# Sheet1.net
KiCad netlist of a schematic drawn in Altium Designer
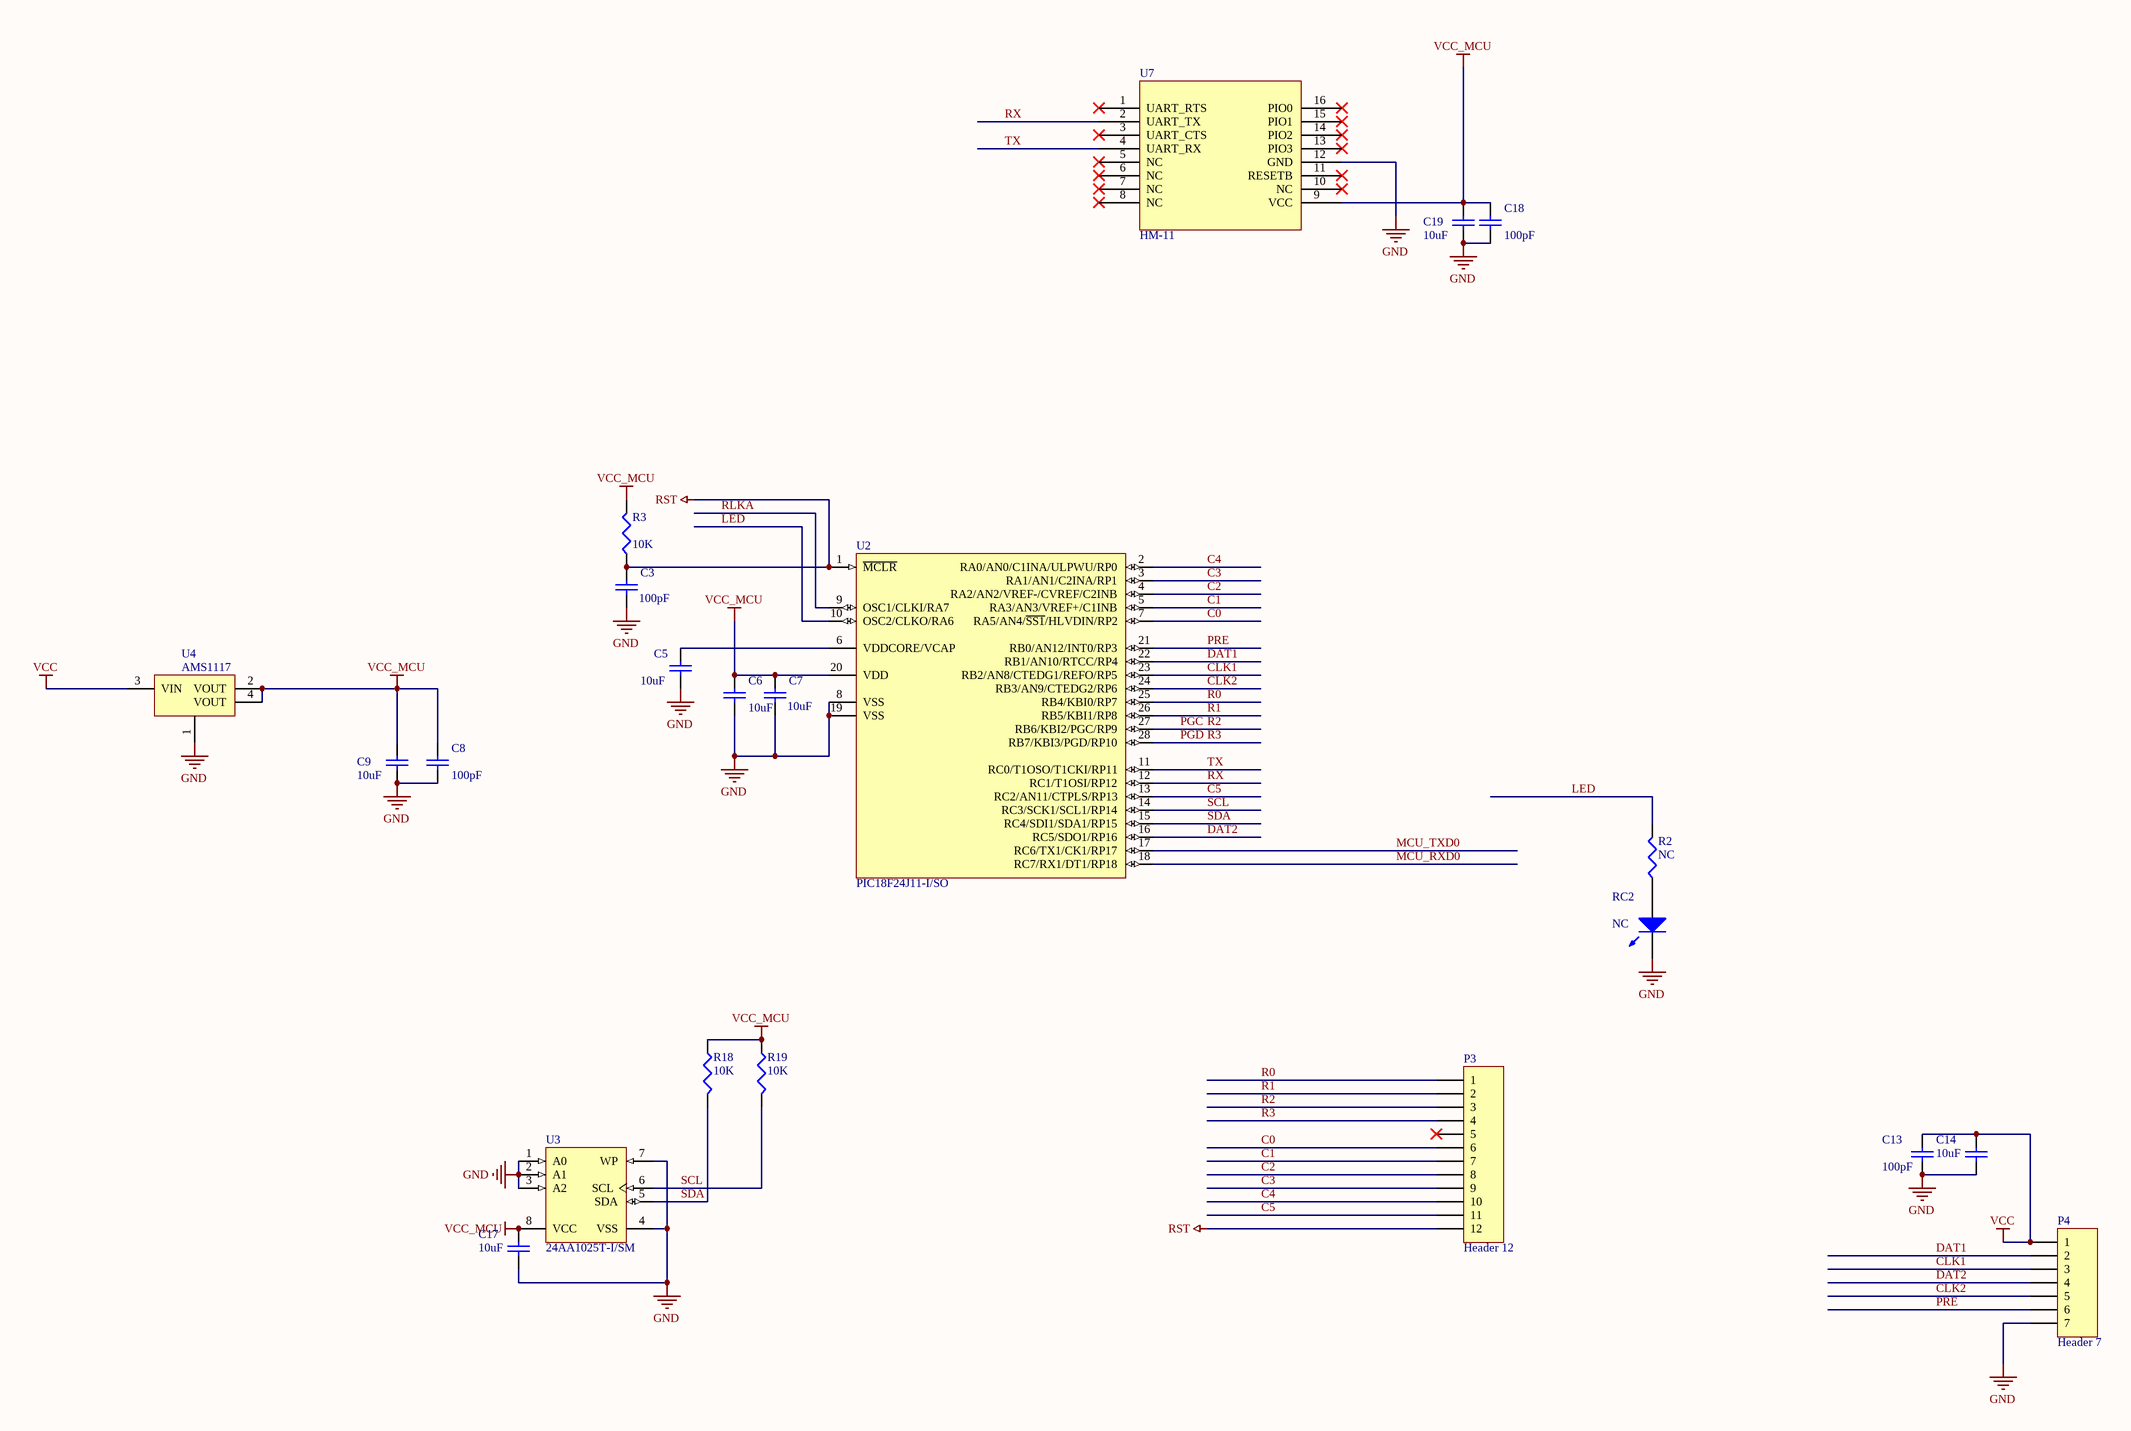
[diagram p0: Sheet1.SchDoc]

(export (version "E")
  (design (tool "Eeschema 10.0.6"))
  (components
    (comp (ref "C3")
      (value "100pF")
      (footprint "CAPC2013X05N")
      (description "0.10µF 50V Ceramic Capacitor Y5V (F) 0805 (2012 Metric) 0.079\" L x 0.049\" W (2.00mm x 1.25mm)")
      (fields (field (name "Comment") "CL21F104ZBCNNNC"))
      (libsource (lib "Miscellaneous Devices") (part "Cap Semi"))
    )
    (comp (ref "C5")
      (value "10uF")
      (footprint "CAPC2013X05N")
      (description "10µF 6.3V Ceramic Capacitor X5R 0805 (2012 Metric) 0.079\" L x 0.049\" W (2.00mm x 1.25mm)")
      (fields (field (name "Comment") "GRM219R60J106KE19D"))
      (libsource (lib "Miscellaneous Devices") (part "Cap Semi"))
    )
    (comp (ref "C6")
      (value "10uF")
      (footprint "CAPC2013X05N")
      (description "10µF 6.3V Ceramic Capacitor X5R 0805 (2012 Metric) 0.079\" L x 0.049\" W (2.00mm x 1.25mm)")
      (fields (field (name "Comment") "GRM219R60J106KE19D"))
      (libsource (lib "Miscellaneous Devices") (part "Cap Semi"))
    )
    (comp (ref "C7")
      (value "10uF")
      (footprint "CAPC2013X05N")
      (description "0.10µF 50V Cera2012 Metric) 0.079\" L x 0.049\" W (2.00mm x 1.25mm)")
      (fields (field (name "Comment") "GRM219R60J106KE19D"))
      (libsource (lib "Miscellaneous Devices") (part "Cap Semi"))
    )
    (comp (ref "C8")
      (value "100pF")
      (footprint "RESC2012L")
      (description "0.10µF 50V Ceramic Capacitor Y5V (F) 0805 (2012 Metric) 0.079\" L x 0.049\" W (2.00mm x 1.25mm)")
      (fields (field (name "Comment") "CL21F104ZBCNNNC"))
      (libsource (lib "Miscellaneous Devices") (part "Cap"))
    )
    (comp (ref "C9")
      (value "10uF")
      (footprint "RESC2012L")
      (description "10µF 6.3V Ceramic Capacitor X5R 0805 (2012 Metric) 0.079\" L x 0.049\" W (2.00mm x 1.25mm)")
      (fields (field (name "Comment") "GRM219R60J106KE19D"))
      (libsource (lib "Miscellaneous Devices") (part "Cap"))
    )
    (comp (ref "C13")
      (value "100pF")
      (footprint "RESC2012L")
      (description "0.10µF 50V Ceramic Capacitor Y5V (F) 0805 (2012 Metric) 0.079\" L x 0.049\" W (2.00mm x 1.25mm)")
      (fields (field (name "Comment") "CL21F104ZBCNNNC"))
      (libsource (lib "Miscellaneous Devices") (part "Cap"))
    )
    (comp (ref "C14")
      (value "10uF")
      (footprint "RESC2012L")
      (description "10µF 6.3V Ceramic Capacitor X5R 0805 (2012 Metric) 0.079\" L x 0.049\" W (2.00mm x 1.25mm)")
      (fields (field (name "Comment") "GRM219R60J106KE19D"))
      (libsource (lib "Miscellaneous Devices") (part "Cap"))
    )
    (comp (ref "C17")
      (value "10uF")
      (footprint "RESC2012L")
      (description "10µF 6.3V Ceramic Capacitor X5R 0805 (2012 Metric) 0.079\" L x 0.049\" W (2.00mm x 1.25mm)")
      (fields (field (name "Comment") "GRM219R60J106KE19D"))
      (libsource (lib "Miscellaneous Devices") (part "Cap"))
    )
    (comp (ref "C18")
      (value "100pF")
      (footprint "CAPC2013X05N")
      (description "0.10µF 50V Ceramic Capacitor Y5V (F) 0805 (2012 Metric) 0.079\" L x 0.049\" W (2.00mm x 1.25mm)")
      (fields (field (name "Comment") "CL21F104ZBCNNNC"))
      (libsource (lib "Miscellaneous Devices") (part "Cap"))
    )
    (comp (ref "C19")
      (value "10uF")
      (footprint "CAPC2013X05N")
      (description "10µF 6.3V Ceramic Capacitor X5R 0805 (2012 Metric) 0.079\" L x 0.049\" W (2.00mm x 1.25mm)")
      (fields (field (name "Comment") "GRM219R60J106KE19D"))
      (libsource (lib "Miscellaneous Devices") (part "Cap"))
    )
    (comp (ref "P3")
      (value "Header 12")
      (footprint "HDR1X12")
      (description "Header, 12-Pin")
      (fields (field (name "PUBLISHER") "Altium Limited"))
      (libsource (lib "Miscellaneous Connectors") (part "Header 12"))
    )
    (comp (ref "P4")
      (value "Header 7")
      (footprint "HDR1X7")
      (description "Header, 7-Pin")
      (fields (field (name "PUBLISHER") "Altium Limited"))
      (libsource (lib "Miscellaneous Connectors") (part "Header 7"))
    )
    (comp (ref "R2")
      (value "NC")
      (footprint "RESC2012L")
      (fields (field (name "PUBLISHER") "Altium Limited"))
      (libsource (lib "Miscellaneous Devices") (part "Res3"))
    )
    (comp (ref "R3")
      (value "10K")
      (footprint "RESC2013X05N")
      (description "RES SMD 10K OHM 5% 1/8W 0805")
      (fields (field (name "Comment") "ERJ-6GEYJ103V"))
      (libsource (lib "Miscellaneous Devices") (part "Res3"))
    )
    (comp (ref "R18")
      (value "10K")
      (footprint "RESC2012L")
      (description "RES SMD 10K OHM 5% 1/8W 0805")
      (fields (field (name "Comment") "ERJ-6GEYJ103V"))
      (libsource (lib "Miscellaneous Devices") (part "Res3"))
    )
    (comp (ref "R19")
      (value "10K")
      (footprint "RESC2012L")
      (description "RES SMD 10K OHM 5% 1/8W 0805")
      (fields (field (name "Comment") "ERJ-6GEYJ103V"))
      (libsource (lib "Miscellaneous Devices") (part "Res3"))
    )
    (comp (ref "RC2")
      (value "NC")
      (footprint "CD3216-1206")
      (description "LED BLUE THRU BOARD 1206")
      (libsource (lib "AM335X_ZCZ") (part "LEDRED1206"))
    )
    (comp (ref "U2")
      (value "PIC18F24J11-I/SO")
      (footprint "SOIC-SO28_N")
      (fields (field (name "PUBLISHER") "Altium Limited"))
      (libsource (lib "Microchip Microcontroller 8-Bit PIC18") (part "PIC18F24J11-I/SO"))
    )
    (comp (ref "U3")
      (value "24AA1025T-I/SM")
      (footprint "SOIJ-SM8_N")
      (description "1 Mbit, 400kHz, 1.7V, I2C Serial EEPROM, 8-Pin SOIC 208mil, Industrial Temperature, Tape and Reel")
      (fields (field (name "PUBLISHER") "Altium Limited"))
      (libsource (lib "Microchip Memory I2C Serial EEPROM") (part "24AA1025T-I/SM"))
    )
    (comp (ref "U4")
      (value "AMS1117")
      (footprint "SOT223-4M")
      (description "Adjustable Precision Shunt Regulator")
      (fields (field (name "PUBLISHER") "Altium Limited"))
      (libsource (lib "Schlib1") (part "AMS1117"))
    )
    (comp (ref "U7") (value "HM-11") (footprint "HM-11") (libsource (lib "Schlib1") (part "HM-11")))
  )
  (nets
    (net (code "1") (name "/C0") (class "Default")
      (node (ref "P3") (pin "6") (pinfunction "6_6") (pintype "passive"))
      (node (ref "U2") (pin "7") (pinfunction "RA5/AN4/~{SS1}/HLVDIN/RP2_7") (pintype "bidirectional"))
    )
    (net (code "2") (name "/C1") (class "Default")
      (node (ref "P3") (pin "7") (pinfunction "7_7") (pintype "passive"))
      (node (ref "U2") (pin "5") (pinfunction "RA3/AN3/VREF+/C1INB_5") (pintype "bidirectional"))
    )
    (net (code "3") (name "/C2") (class "Default")
      (node (ref "P3") (pin "8") (pinfunction "8_8") (pintype "passive"))
      (node (ref "U2") (pin "4") (pinfunction "RA2/AN2/VREF-/CVREF/C2INB_4") (pintype "bidirectional"))
    )
    (net (code "4") (name "/C3") (class "Default")
      (node (ref "P3") (pin "9") (pinfunction "9_9") (pintype "passive"))
      (node (ref "U2") (pin "3") (pinfunction "RA1/AN1/C2INA/RP1_3") (pintype "bidirectional"))
    )
    (net (code "5") (name "/C4") (class "Default")
      (node (ref "P3") (pin "10") (pinfunction "10_10") (pintype "passive"))
      (node (ref "U2") (pin "2") (pinfunction "RA0/AN0/C1INA/ULPWU/RP0_2") (pintype "bidirectional"))
    )
    (net (code "6") (name "/C5") (class "Default")
      (node (ref "P3") (pin "11") (pinfunction "11_11") (pintype "passive"))
      (node (ref "U2") (pin "13") (pinfunction "RC2/AN11/CTPLS/RP13_13") (pintype "bidirectional"))
    )
    (net (code "7") (name "/CLK1") (class "Default")
      (node (ref "P4") (pin "3") (pinfunction "3_3") (pintype "passive"))
      (node (ref "U2") (pin "23") (pinfunction "RB2/AN8/CTEDG1/REFO/RP5_23") (pintype "bidirectional"))
    )
    (net (code "8") (name "/CLK2") (class "Default")
      (node (ref "P4") (pin "5") (pinfunction "5_5") (pintype "passive"))
      (node (ref "U2") (pin "24") (pinfunction "RB3/AN9/CTEDG2/RP6_24") (pintype "bidirectional"))
    )
    (net (code "9") (name "/DAT1") (class "Default")
      (node (ref "P4") (pin "2") (pinfunction "2_2") (pintype "passive"))
      (node (ref "U2") (pin "22") (pinfunction "RB1/AN10/RTCC/RP4_22") (pintype "bidirectional"))
    )
    (net (code "10") (name "/DAT2") (class "Default")
      (node (ref "P4") (pin "4") (pinfunction "4_4") (pintype "passive"))
      (node (ref "U2") (pin "16") (pinfunction "RC5/SDO1/RP16_16") (pintype "bidirectional"))
    )
    (net (code "11") (name "/LED") (class "Default")
      (node (ref "R2") (pin "1") (pinfunction "1_1") (pintype "passive"))
      (node (ref "U2") (pin "10") (pinfunction "OSC2/CLKO/RA6_10") (pintype "bidirectional"))
    )
    (net (code "12") (name "/MCU_RXD0") (class "Default")
      (node (ref "U2") (pin "18") (pinfunction "RC7/RX1/DT1/RP18_18") (pintype "bidirectional"))
    )
    (net (code "13") (name "/MCU_TXD0") (class "Default")
      (node (ref "U2") (pin "17") (pinfunction "RC6/TX1/CK1/RP17_17") (pintype "bidirectional"))
    )
    (net (code "14") (name "/PGC") (class "Default")
      (node (ref "P3") (pin "3") (pinfunction "3_3") (pintype "passive"))
      (node (ref "U2") (pin "27") (pinfunction "RB6/KBI2/PGC/RP9_27") (pintype "bidirectional"))
    )
    (net (code "15") (name "/PGD") (class "Default")
      (node (ref "P3") (pin "4") (pinfunction "4_4") (pintype "passive"))
      (node (ref "U2") (pin "28") (pinfunction "RB7/KBI3/PGD/RP10_28") (pintype "bidirectional"))
    )
    (net (code "16") (name "/PRE") (class "Default")
      (node (ref "P4") (pin "6") (pinfunction "6_6") (pintype "passive"))
      (node (ref "U2") (pin "21") (pinfunction "RB0/AN12/INT0/RP3_21") (pintype "bidirectional"))
    )
    (net (code "17") (name "/R0") (class "Default")
      (node (ref "P3") (pin "1") (pinfunction "1_1") (pintype "passive"))
      (node (ref "U2") (pin "25") (pinfunction "RB4/KBI0/RP7_25") (pintype "bidirectional"))
    )
    (net (code "18") (name "/R1") (class "Default")
      (node (ref "P3") (pin "2") (pinfunction "2_2") (pintype "passive"))
      (node (ref "U2") (pin "26") (pinfunction "RB5/KBI1/RP8_26") (pintype "bidirectional"))
    )
    (net (code "19") (name "/RLKA") (class "Default")
      (node (ref "U2") (pin "9") (pinfunction "OSC1/CLKI/RA7_9") (pintype "bidirectional"))
    )
    (net (code "20") (name "/RX") (class "Default")
      (node (ref "U2") (pin "12") (pinfunction "RC1/T1OSI/RP12_12") (pintype "bidirectional"))
      (node (ref "U7") (pin "2") (pinfunction "UART_TX_2") (pintype "passive"))
    )
    (net (code "21") (name "/SCL") (class "Default")
      (node (ref "R19") (pin "1") (pinfunction "1_1") (pintype "passive"))
      (node (ref "U2") (pin "14") (pinfunction "RC3/SCK1/SCL1/RP14_14") (pintype "bidirectional"))
      (node (ref "U3") (pin "6") (pinfunction "SCL_6") (pintype "input"))
    )
    (net (code "22") (name "/SDA") (class "Default")
      (node (ref "R18") (pin "1") (pinfunction "1_1") (pintype "passive"))
      (node (ref "U2") (pin "15") (pinfunction "RC4/SDI1/SDA1/RP15_15") (pintype "bidirectional"))
      (node (ref "U3") (pin "5") (pinfunction "SDA_5") (pintype "bidirectional"))
    )
    (net (code "23") (name "/TX") (class "Default")
      (node (ref "U2") (pin "11") (pinfunction "RC0/T1OSO/T1CKI/RP11_11") (pintype "bidirectional"))
      (node (ref "U7") (pin "4") (pinfunction "UART_RX_4") (pintype "passive"))
    )
    (net (code "24") (name "GND") (class "Default")
      (node (ref "C13") (pin "2") (pinfunction "2_2") (pintype "passive"))
      (node (ref "C14") (pin "2") (pinfunction "2_2") (pintype "passive"))
      (node (ref "C17") (pin "2") (pinfunction "2_2") (pintype "passive"))
      (node (ref "C18") (pin "2") (pinfunction "2_2") (pintype "passive"))
      (node (ref "C19") (pin "2") (pinfunction "2_2") (pintype "passive"))
      (node (ref "C3") (pin "1") (pinfunction "1_1") (pintype "passive"))
      (node (ref "C5") (pin "1") (pinfunction "1_1") (pintype "passive"))
      (node (ref "C6") (pin "1") (pinfunction "1_1") (pintype "passive"))
      (node (ref "C7") (pin "1") (pinfunction "1_1") (pintype "passive"))
      (node (ref "C8") (pin "2") (pinfunction "2_2") (pintype "passive"))
      (node (ref "C9") (pin "2") (pinfunction "2_2") (pintype "passive"))
      (node (ref "P4") (pin "7") (pinfunction "7_7") (pintype "passive"))
      (node (ref "RC2") (pin "2") (pinfunction "K_2") (pintype "passive"))
      (node (ref "U2") (pin "19") (pinfunction "VSS_19") (pintype "power_in"))
      (node (ref "U2") (pin "8") (pinfunction "VSS_8") (pintype "power_in"))
      (node (ref "U3") (pin "1") (pinfunction "A0_1") (pintype "input"))
      (node (ref "U3") (pin "2") (pinfunction "A1_2") (pintype "input"))
      (node (ref "U3") (pin "3") (pinfunction "A2_3") (pintype "input"))
      (node (ref "U3") (pin "4") (pinfunction "VSS_4") (pintype "power_in"))
      (node (ref "U3") (pin "7") (pinfunction "WP_7") (pintype "input"))
      (node (ref "U4") (pin "1") (pinfunction "GND_1") (pintype "power_in"))
      (node (ref "U7") (pin "12") (pinfunction "GND_12") (pintype "passive"))
    )
    (net (code "25") (name "Net-(RC2-A)") (class "Default")
      (node (ref "R2") (pin "2") (pinfunction "2_2") (pintype "passive"))
      (node (ref "RC2") (pin "1") (pinfunction "A_1") (pintype "passive"))
    )
    (net (code "26") (name "Net-(U2-VDDCORE{slash}VCAP)") (class "Default")
      (node (ref "C5") (pin "2") (pinfunction "2_2") (pintype "passive"))
      (node (ref "U2") (pin "6") (pinfunction "VDDCORE/VCAP_6") (pintype "power_in"))
    )
    (net (code "27") (name "RST") (class "Default")
      (node (ref "C3") (pin "2") (pinfunction "2_2") (pintype "passive"))
      (node (ref "P3") (pin "12") (pinfunction "12_12") (pintype "passive"))
      (node (ref "R3") (pin "1") (pinfunction "1_1") (pintype "passive"))
      (node (ref "U2") (pin "1") (pinfunction "~{MCLR}_1") (pintype "input"))
    )
    (net (code "28") (name "VCC") (class "Default")
      (node (ref "C13") (pin "1") (pinfunction "1_1") (pintype "passive"))
      (node (ref "C14") (pin "1") (pinfunction "1_1") (pintype "passive"))
      (node (ref "P4") (pin "1") (pinfunction "1_1") (pintype "passive"))
      (node (ref "U4") (pin "3") (pinfunction "VIN_3") (pintype "power_in"))
    )
    (net (code "29") (name "VCC_MCU") (class "Default")
      (node (ref "C17") (pin "1") (pinfunction "1_1") (pintype "passive"))
      (node (ref "C18") (pin "1") (pinfunction "1_1") (pintype "passive"))
      (node (ref "C19") (pin "1") (pinfunction "1_1") (pintype "passive"))
      (node (ref "C6") (pin "2") (pinfunction "2_2") (pintype "passive"))
      (node (ref "C7") (pin "2") (pinfunction "2_2") (pintype "passive"))
      (node (ref "C8") (pin "1") (pinfunction "1_1") (pintype "passive"))
      (node (ref "C9") (pin "1") (pinfunction "1_1") (pintype "passive"))
      (node (ref "R18") (pin "2") (pinfunction "2_2") (pintype "passive"))
      (node (ref "R19") (pin "2") (pinfunction "2_2") (pintype "passive"))
      (node (ref "R3") (pin "2") (pinfunction "2_2") (pintype "passive"))
      (node (ref "U2") (pin "20") (pinfunction "VDD_20") (pintype "power_in"))
      (node (ref "U3") (pin "8") (pinfunction "VCC_8") (pintype "power_in"))
      (node (ref "U4") (pin "2") (pinfunction "VOUT_2") (pintype "power_in"))
      (node (ref "U4") (pin "4") (pinfunction "VOUT_4") (pintype "power_in"))
      (node (ref "U7") (pin "9") (pinfunction "VCC_9") (pintype "passive"))
    )
    (net (code "30") (name "unconnected-(P3-Pad5)") (class "Default")
      (node (ref "P3") (pin "5") (pinfunction "5_5") (pintype "passive+no_connect"))
    )
    (net (code "31") (name "unconnected-(U7-NC-Pad5)") (class "Default")
      (node (ref "U7") (pin "5") (pinfunction "NC_5") (pintype "passive+no_connect"))
    )
    (net (code "32") (name "unconnected-(U7-NC-Pad6)") (class "Default")
      (node (ref "U7") (pin "6") (pinfunction "NC_6") (pintype "passive+no_connect"))
    )
    (net (code "33") (name "unconnected-(U7-NC-Pad7)") (class "Default")
      (node (ref "U7") (pin "7") (pinfunction "NC_7") (pintype "passive+no_connect"))
    )
    (net (code "34") (name "unconnected-(U7-NC-Pad8)") (class "Default")
      (node (ref "U7") (pin "8") (pinfunction "NC_8") (pintype "passive+no_connect"))
    )
    (net (code "35") (name "unconnected-(U7-NC-Pad10)") (class "Default")
      (node (ref "U7") (pin "10") (pinfunction "NC_10") (pintype "passive+no_connect"))
    )
    (net (code "36") (name "unconnected-(U7-PIO0-Pad16)") (class "Default")
      (node (ref "U7") (pin "16") (pinfunction "PIO0_16") (pintype "passive+no_connect"))
    )
    (net (code "37") (name "unconnected-(U7-PIO1-Pad15)") (class "Default")
      (node (ref "U7") (pin "15") (pinfunction "PIO1_15") (pintype "passive+no_connect"))
    )
    (net (code "38") (name "unconnected-(U7-PIO2-Pad14)") (class "Default")
      (node (ref "U7") (pin "14") (pinfunction "PIO2_14") (pintype "passive+no_connect"))
    )
    (net (code "39") (name "unconnected-(U7-PIO3-Pad13)") (class "Default")
      (node (ref "U7") (pin "13") (pinfunction "PIO3_13") (pintype "passive+no_connect"))
    )
    (net (code "40") (name "unconnected-(U7-RESETB-Pad11)") (class "Default")
      (node (ref "U7") (pin "11") (pinfunction "RESETB_11") (pintype "passive+no_connect"))
    )
    (net (code "41") (name "unconnected-(U7-UART_CTS-Pad3)") (class "Default")
      (node (ref "U7") (pin "3") (pinfunction "UART_CTS_3") (pintype "passive+no_connect"))
    )
    (net (code "42") (name "unconnected-(U7-UART_RTS-Pad1)") (class "Default")
      (node (ref "U7") (pin "1") (pinfunction "UART_RTS_1") (pintype "passive+no_connect"))
    )
  )
)
